# cpubus.net
KiCad netlist of a schematic drawn in EAGLE
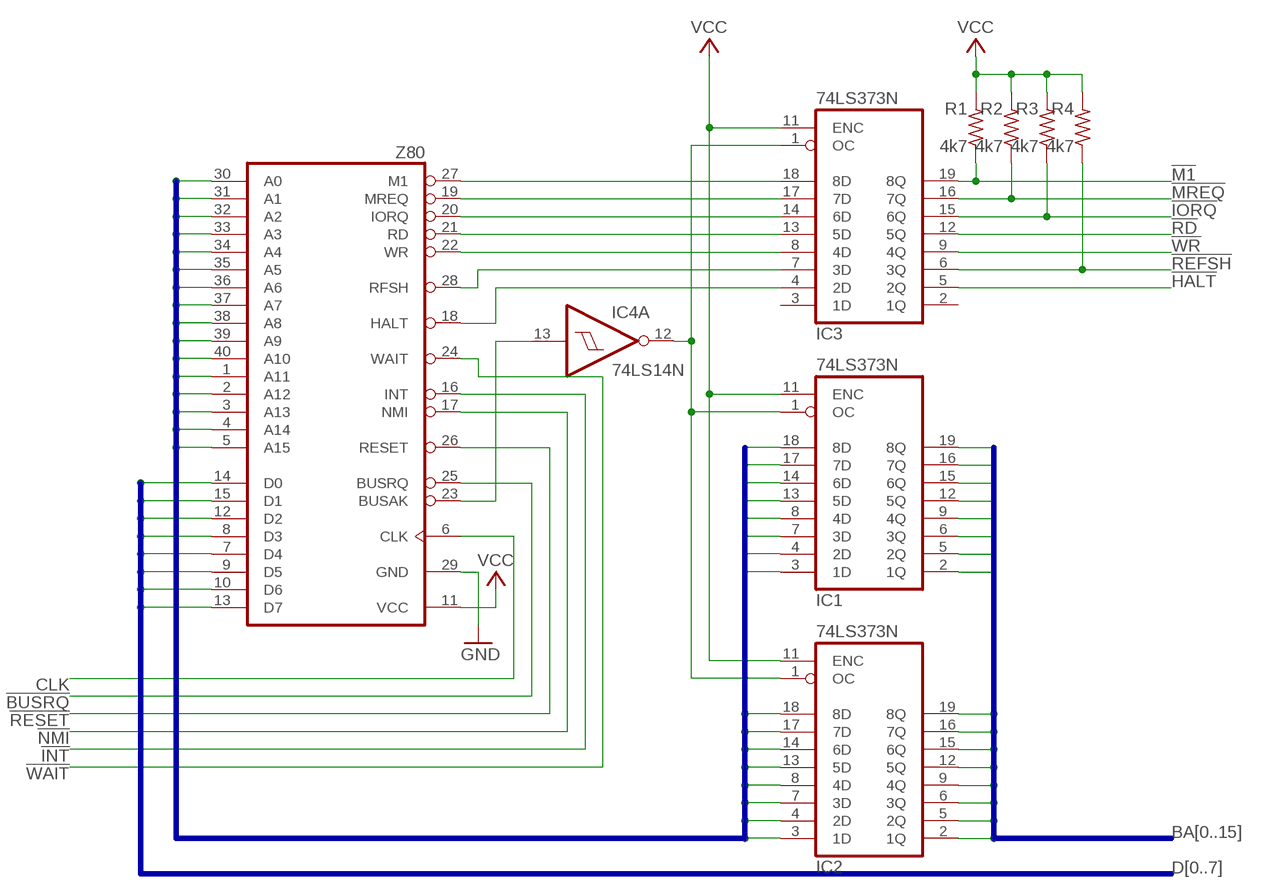
[diagram p0: schematic, sheet 1]

(export (version "E")
  (design (tool "Eeschema 10.0.6"))
  (components
    (comp (ref "IC1")
      (value "74LS373N")
      (footprint "eagle-import:DIL20")
      (libsource (lib "eagle-import") (part "74373NLS"))
    )
    (comp (ref "IC2")
      (value "74LS373N")
      (footprint "eagle-import:DIL20")
      (libsource (lib "eagle-import") (part "74373NLS"))
    )
    (comp (ref "IC3")
      (value "74LS373N")
      (footprint "eagle-import:DIL20")
      (libsource (lib "eagle-import") (part "74373NLS"))
    )
    (comp (ref "IC4")
      (value "74LS14N")
      (footprint "eagle-import:DIL14")
      (libsource (lib "eagle-import") (part "7414NLS"))
    )
    (comp (ref "R1")
      (value "4k7")
      (footprint "eagle-import:0204_7")
      (libsource (lib "eagle-import") (part "R-US_0204/7"))
    )
    (comp (ref "R2")
      (value "4k7")
      (footprint "eagle-import:0204_7")
      (libsource (lib "eagle-import") (part "R-US_0204/7"))
    )
    (comp (ref "R3")
      (value "4k7")
      (footprint "eagle-import:0204_7")
      (libsource (lib "eagle-import") (part "R-US_0204/7"))
    )
    (comp (ref "R4")
      (value "4k7")
      (footprint "eagle-import:0204_7")
      (libsource (lib "eagle-import") (part "R-US_0204/7"))
    )
    (comp (ref "Z80")
      (value "Z80CPU")
      (footprint "eagle-import:DIL40")
      (libsource (lib "eagle-import") (part "Z80CPU"))
    )
  )
  (nets
    (net (code "25") (name "/A0") (class "Default")
      (node (ref "IC1") (pin "18") (pinfunction "8D_18") (pintype "input"))
      (node (ref "Z80") (pin "30") (pinfunction "A0_30") (pintype "output"))
    )
    (net (code "26") (name "/A1") (class "Default")
      (node (ref "IC1") (pin "17") (pinfunction "7D_17") (pintype "input"))
      (node (ref "Z80") (pin "31") (pinfunction "A1_31") (pintype "output"))
    )
    (net (code "27") (name "/A2") (class "Default")
      (node (ref "IC1") (pin "14") (pinfunction "6D_14") (pintype "input"))
      (node (ref "Z80") (pin "32") (pinfunction "A2_32") (pintype "output"))
    )
    (net (code "28") (name "/A3") (class "Default")
      (node (ref "IC1") (pin "13") (pinfunction "5D_13") (pintype "input"))
      (node (ref "Z80") (pin "33") (pinfunction "A3_33") (pintype "output"))
    )
    (net (code "29") (name "/A4") (class "Default")
      (node (ref "IC1") (pin "8") (pinfunction "4D_8") (pintype "input"))
      (node (ref "Z80") (pin "34") (pinfunction "A4_34") (pintype "output"))
    )
    (net (code "30") (name "/A5") (class "Default")
      (node (ref "IC1") (pin "7") (pinfunction "3D_7") (pintype "input"))
      (node (ref "Z80") (pin "35") (pinfunction "A5_35") (pintype "output"))
    )
    (net (code "31") (name "/A6") (class "Default")
      (node (ref "IC1") (pin "4") (pinfunction "2D_4") (pintype "input"))
      (node (ref "Z80") (pin "36") (pinfunction "A6_36") (pintype "output"))
    )
    (net (code "32") (name "/A7") (class "Default")
      (node (ref "IC1") (pin "3") (pinfunction "1D_3") (pintype "input"))
      (node (ref "Z80") (pin "37") (pinfunction "A7_37") (pintype "output"))
    )
    (net (code "33") (name "/A8") (class "Default")
      (node (ref "IC2") (pin "18") (pinfunction "8D_18") (pintype "input"))
      (node (ref "Z80") (pin "38") (pinfunction "A8_38") (pintype "output"))
    )
    (net (code "34") (name "/A9") (class "Default")
      (node (ref "IC2") (pin "17") (pinfunction "7D_17") (pintype "input"))
      (node (ref "Z80") (pin "39") (pinfunction "A9_39") (pintype "output"))
    )
    (net (code "35") (name "/A10") (class "Default")
      (node (ref "IC2") (pin "14") (pinfunction "6D_14") (pintype "input"))
      (node (ref "Z80") (pin "40") (pinfunction "A10_40") (pintype "output"))
    )
    (net (code "36") (name "/A11") (class "Default")
      (node (ref "IC2") (pin "13") (pinfunction "5D_13") (pintype "input"))
      (node (ref "Z80") (pin "1") (pinfunction "A11_1") (pintype "output"))
    )
    (net (code "37") (name "/A12") (class "Default")
      (node (ref "IC2") (pin "8") (pinfunction "4D_8") (pintype "input"))
      (node (ref "Z80") (pin "2") (pinfunction "A12_2") (pintype "output"))
    )
    (net (code "38") (name "/A13") (class "Default")
      (node (ref "IC2") (pin "7") (pinfunction "3D_7") (pintype "input"))
      (node (ref "Z80") (pin "3") (pinfunction "A13_3") (pintype "output"))
    )
    (net (code "39") (name "/A14") (class "Default")
      (node (ref "IC2") (pin "4") (pinfunction "2D_4") (pintype "input"))
      (node (ref "Z80") (pin "4") (pinfunction "A14_4") (pintype "output"))
    )
    (net (code "40") (name "/A15") (class "Default")
      (node (ref "IC2") (pin "3") (pinfunction "1D_3") (pintype "input"))
      (node (ref "Z80") (pin "5") (pinfunction "A15_5") (pintype "output"))
    )
    (net (code "42") (name "/CLK") (class "Default")
      (node (ref "Z80") (pin "6") (pinfunction "CLK_6") (pintype "input"))
    )
    (net (code "44") (name "/~{BUSRQ}") (class "Default")
      (node (ref "Z80") (pin "25") (pinfunction "BUSRQ_25") (pintype "input"))
    )
    (net (code "45") (name "/~{HALT}") (class "Default")
      (node (ref "IC3") (pin "5") (pinfunction "2Q_5") (pintype "tri_state"))
    )
    (net (code "46") (name "/~{INT}") (class "Default")
      (node (ref "Z80") (pin "16") (pinfunction "INT_16") (pintype "input"))
    )
    (net (code "47") (name "/~{IORQ}") (class "Default")
      (node (ref "IC3") (pin "15") (pinfunction "6Q_15") (pintype "tri_state"))
      (node (ref "R3") (pin "1") (pinfunction "1_1") (pintype "passive"))
    )
    (net (code "48") (name "/~{M1}") (class "Default")
      (node (ref "IC3") (pin "19") (pinfunction "8Q_19") (pintype "tri_state"))
      (node (ref "R1") (pin "1") (pinfunction "1_1") (pintype "passive"))
    )
    (net (code "49") (name "/~{MREQ}") (class "Default")
      (node (ref "IC3") (pin "16") (pinfunction "7Q_16") (pintype "tri_state"))
      (node (ref "R2") (pin "1") (pinfunction "1_1") (pintype "passive"))
    )
    (net (code "50") (name "/~{NMI}") (class "Default")
      (node (ref "Z80") (pin "17") (pinfunction "NMI_17") (pintype "input"))
    )
    (net (code "51") (name "/~{RD}") (class "Default")
      (node (ref "IC3") (pin "12") (pinfunction "5Q_12") (pintype "tri_state"))
    )
    (net (code "52") (name "/~{REFSH}") (class "Default")
      (node (ref "IC3") (pin "6") (pinfunction "3Q_6") (pintype "tri_state"))
      (node (ref "R4") (pin "1") (pinfunction "1_1") (pintype "passive"))
    )
    (net (code "53") (name "/~{RESET}") (class "Default")
      (node (ref "Z80") (pin "26") (pinfunction "RESET_26") (pintype "input"))
    )
    (net (code "54") (name "/~{WAIT}") (class "Default")
      (node (ref "Z80") (pin "24") (pinfunction "WAIT_24") (pintype "input"))
    )
    (net (code "55") (name "/~{WR}") (class "Default")
      (node (ref "IC3") (pin "9") (pinfunction "4Q_9") (pintype "tri_state"))
    )
    (net (code "56") (name "GND") (class "Default")
      (node (ref "Z80") (pin "29") (pinfunction "GND_29") (pintype "power_in"))
    )
    (net (code "57") (name "Net-(IC1A-OC)") (class "Default")
      (node (ref "IC1") (pin "1") (pinfunction "OC_1") (pintype "input"))
      (node (ref "IC2") (pin "1") (pinfunction "OC_1") (pintype "input"))
      (node (ref "IC3") (pin "1") (pinfunction "OC_1") (pintype "input"))
      (node (ref "IC4") (pin "12") (pinfunction "O_12") (pintype "output"))
    )
    (net (code "58") (name "Net-(IC3A-2D)") (class "Default")
      (node (ref "IC3") (pin "4") (pinfunction "2D_4") (pintype "input"))
      (node (ref "Z80") (pin "18") (pinfunction "HALT_18") (pintype "output"))
    )
    (net (code "59") (name "Net-(IC3A-3D)") (class "Default")
      (node (ref "IC3") (pin "7") (pinfunction "3D_7") (pintype "input"))
      (node (ref "Z80") (pin "28") (pinfunction "RFSH_28") (pintype "output"))
    )
    (net (code "60") (name "Net-(IC3A-4D)") (class "Default")
      (node (ref "IC3") (pin "8") (pinfunction "4D_8") (pintype "input"))
      (node (ref "Z80") (pin "22") (pinfunction "WR_22") (pintype "output"))
    )
    (net (code "61") (name "Net-(IC3A-5D)") (class "Default")
      (node (ref "IC3") (pin "13") (pinfunction "5D_13") (pintype "input"))
      (node (ref "Z80") (pin "21") (pinfunction "RD_21") (pintype "output"))
    )
    (net (code "62") (name "Net-(IC3A-6D)") (class "Default")
      (node (ref "IC3") (pin "14") (pinfunction "6D_14") (pintype "input"))
      (node (ref "Z80") (pin "20") (pinfunction "IORQ_20") (pintype "output"))
    )
    (net (code "63") (name "Net-(IC3A-7D)") (class "Default")
      (node (ref "IC3") (pin "17") (pinfunction "7D_17") (pintype "input"))
      (node (ref "Z80") (pin "19") (pinfunction "MREQ_19") (pintype "output"))
    )
    (net (code "64") (name "Net-(IC3A-8D)") (class "Default")
      (node (ref "IC3") (pin "18") (pinfunction "8D_18") (pintype "input"))
      (node (ref "Z80") (pin "27") (pinfunction "M1_27") (pintype "output"))
    )
    (net (code "65") (name "Net-(IC4A-I)") (class "Default")
      (node (ref "IC4") (pin "13") (pinfunction "I_13") (pintype "input"))
      (node (ref "Z80") (pin "23") (pinfunction "BUSAK_23") (pintype "output"))
    )
    (net (code "66") (name "VCC") (class "Default")
      (node (ref "IC1") (pin "11") (pinfunction "ENC_11") (pintype "input"))
      (node (ref "IC2") (pin "11") (pinfunction "ENC_11") (pintype "input"))
      (node (ref "IC3") (pin "11") (pinfunction "ENC_11") (pintype "input"))
      (node (ref "R1") (pin "2") (pinfunction "2_2") (pintype "passive"))
      (node (ref "R2") (pin "2") (pinfunction "2_2") (pintype "passive"))
      (node (ref "R3") (pin "2") (pinfunction "2_2") (pintype "passive"))
      (node (ref "R4") (pin "2") (pinfunction "2_2") (pintype "passive"))
      (node (ref "Z80") (pin "11") (pinfunction "VCC_11") (pintype "power_in"))
    )
    (net (code "67") (name "unconnected-(IC1A-1Q-Pad2)") (class "Default")
      (node (ref "IC1") (pin "2") (pinfunction "1Q_2") (pintype "tri_state"))
    )
    (net (code "68") (name "unconnected-(IC1A-2Q-Pad5)") (class "Default")
      (node (ref "IC1") (pin "5") (pinfunction "2Q_5") (pintype "tri_state"))
    )
    (net (code "69") (name "unconnected-(IC1A-3Q-Pad6)") (class "Default")
      (node (ref "IC1") (pin "6") (pinfunction "3Q_6") (pintype "tri_state"))
    )
    (net (code "70") (name "unconnected-(IC1A-4Q-Pad9)") (class "Default")
      (node (ref "IC1") (pin "9") (pinfunction "4Q_9") (pintype "tri_state"))
    )
    (net (code "71") (name "unconnected-(IC1A-5Q-Pad12)") (class "Default")
      (node (ref "IC1") (pin "12") (pinfunction "5Q_12") (pintype "tri_state"))
    )
    (net (code "72") (name "unconnected-(IC1A-6Q-Pad15)") (class "Default")
      (node (ref "IC1") (pin "15") (pinfunction "6Q_15") (pintype "tri_state"))
    )
    (net (code "73") (name "unconnected-(IC1A-7Q-Pad16)") (class "Default")
      (node (ref "IC1") (pin "16") (pinfunction "7Q_16") (pintype "tri_state"))
    )
    (net (code "74") (name "unconnected-(IC1A-8Q-Pad19)") (class "Default")
      (node (ref "IC1") (pin "19") (pinfunction "8Q_19") (pintype "tri_state"))
    )
    (net (code "75") (name "unconnected-(IC2A-1Q-Pad2)") (class "Default")
      (node (ref "IC2") (pin "2") (pinfunction "1Q_2") (pintype "tri_state"))
    )
    (net (code "76") (name "unconnected-(IC2A-2Q-Pad5)") (class "Default")
      (node (ref "IC2") (pin "5") (pinfunction "2Q_5") (pintype "tri_state"))
    )
    (net (code "77") (name "unconnected-(IC2A-3Q-Pad6)") (class "Default")
      (node (ref "IC2") (pin "6") (pinfunction "3Q_6") (pintype "tri_state"))
    )
    (net (code "78") (name "unconnected-(IC2A-4Q-Pad9)") (class "Default")
      (node (ref "IC2") (pin "9") (pinfunction "4Q_9") (pintype "tri_state"))
    )
    (net (code "79") (name "unconnected-(IC2A-5Q-Pad12)") (class "Default")
      (node (ref "IC2") (pin "12") (pinfunction "5Q_12") (pintype "tri_state"))
    )
    (net (code "80") (name "unconnected-(IC2A-6Q-Pad15)") (class "Default")
      (node (ref "IC2") (pin "15") (pinfunction "6Q_15") (pintype "tri_state"))
    )
    (net (code "81") (name "unconnected-(IC2A-7Q-Pad16)") (class "Default")
      (node (ref "IC2") (pin "16") (pinfunction "7Q_16") (pintype "tri_state"))
    )
    (net (code "82") (name "unconnected-(IC2A-8Q-Pad19)") (class "Default")
      (node (ref "IC2") (pin "19") (pinfunction "8Q_19") (pintype "tri_state"))
    )
    (net (code "83") (name "unconnected-(IC3A-1D-Pad3)") (class "Default")
      (node (ref "IC3") (pin "3") (pinfunction "1D_3") (pintype "input"))
    )
    (net (code "84") (name "unconnected-(IC3A-1Q-Pad2)") (class "Default")
      (node (ref "IC3") (pin "2") (pinfunction "1Q_2") (pintype "tri_state"))
    )
    (net (code "85") (name "unconnected-(Z80-D0-Pad14)") (class "Default")
      (node (ref "Z80") (pin "14") (pinfunction "D0_14") (pintype "bidirectional"))
    )
    (net (code "86") (name "unconnected-(Z80-D1-Pad15)") (class "Default")
      (node (ref "Z80") (pin "15") (pinfunction "D1_15") (pintype "bidirectional"))
    )
    (net (code "87") (name "unconnected-(Z80-D2-Pad12)") (class "Default")
      (node (ref "Z80") (pin "12") (pinfunction "D2_12") (pintype "bidirectional"))
    )
    (net (code "88") (name "unconnected-(Z80-D3-Pad8)") (class "Default")
      (node (ref "Z80") (pin "8") (pinfunction "D3_8") (pintype "bidirectional"))
    )
    (net (code "89") (name "unconnected-(Z80-D4-Pad7)") (class "Default")
      (node (ref "Z80") (pin "7") (pinfunction "D4_7") (pintype "bidirectional"))
    )
    (net (code "90") (name "unconnected-(Z80-D5-Pad9)") (class "Default")
      (node (ref "Z80") (pin "9") (pinfunction "D5_9") (pintype "bidirectional"))
    )
    (net (code "91") (name "unconnected-(Z80-D6-Pad10)") (class "Default")
      (node (ref "Z80") (pin "10") (pinfunction "D6_10") (pintype "bidirectional"))
    )
    (net (code "92") (name "unconnected-(Z80-D7-Pad13)") (class "Default")
      (node (ref "Z80") (pin "13") (pinfunction "D7_13") (pintype "bidirectional"))
    )
  )
)
